# ESP_flagServer.net
KiCad netlist of a schematic drawn in EAGLE
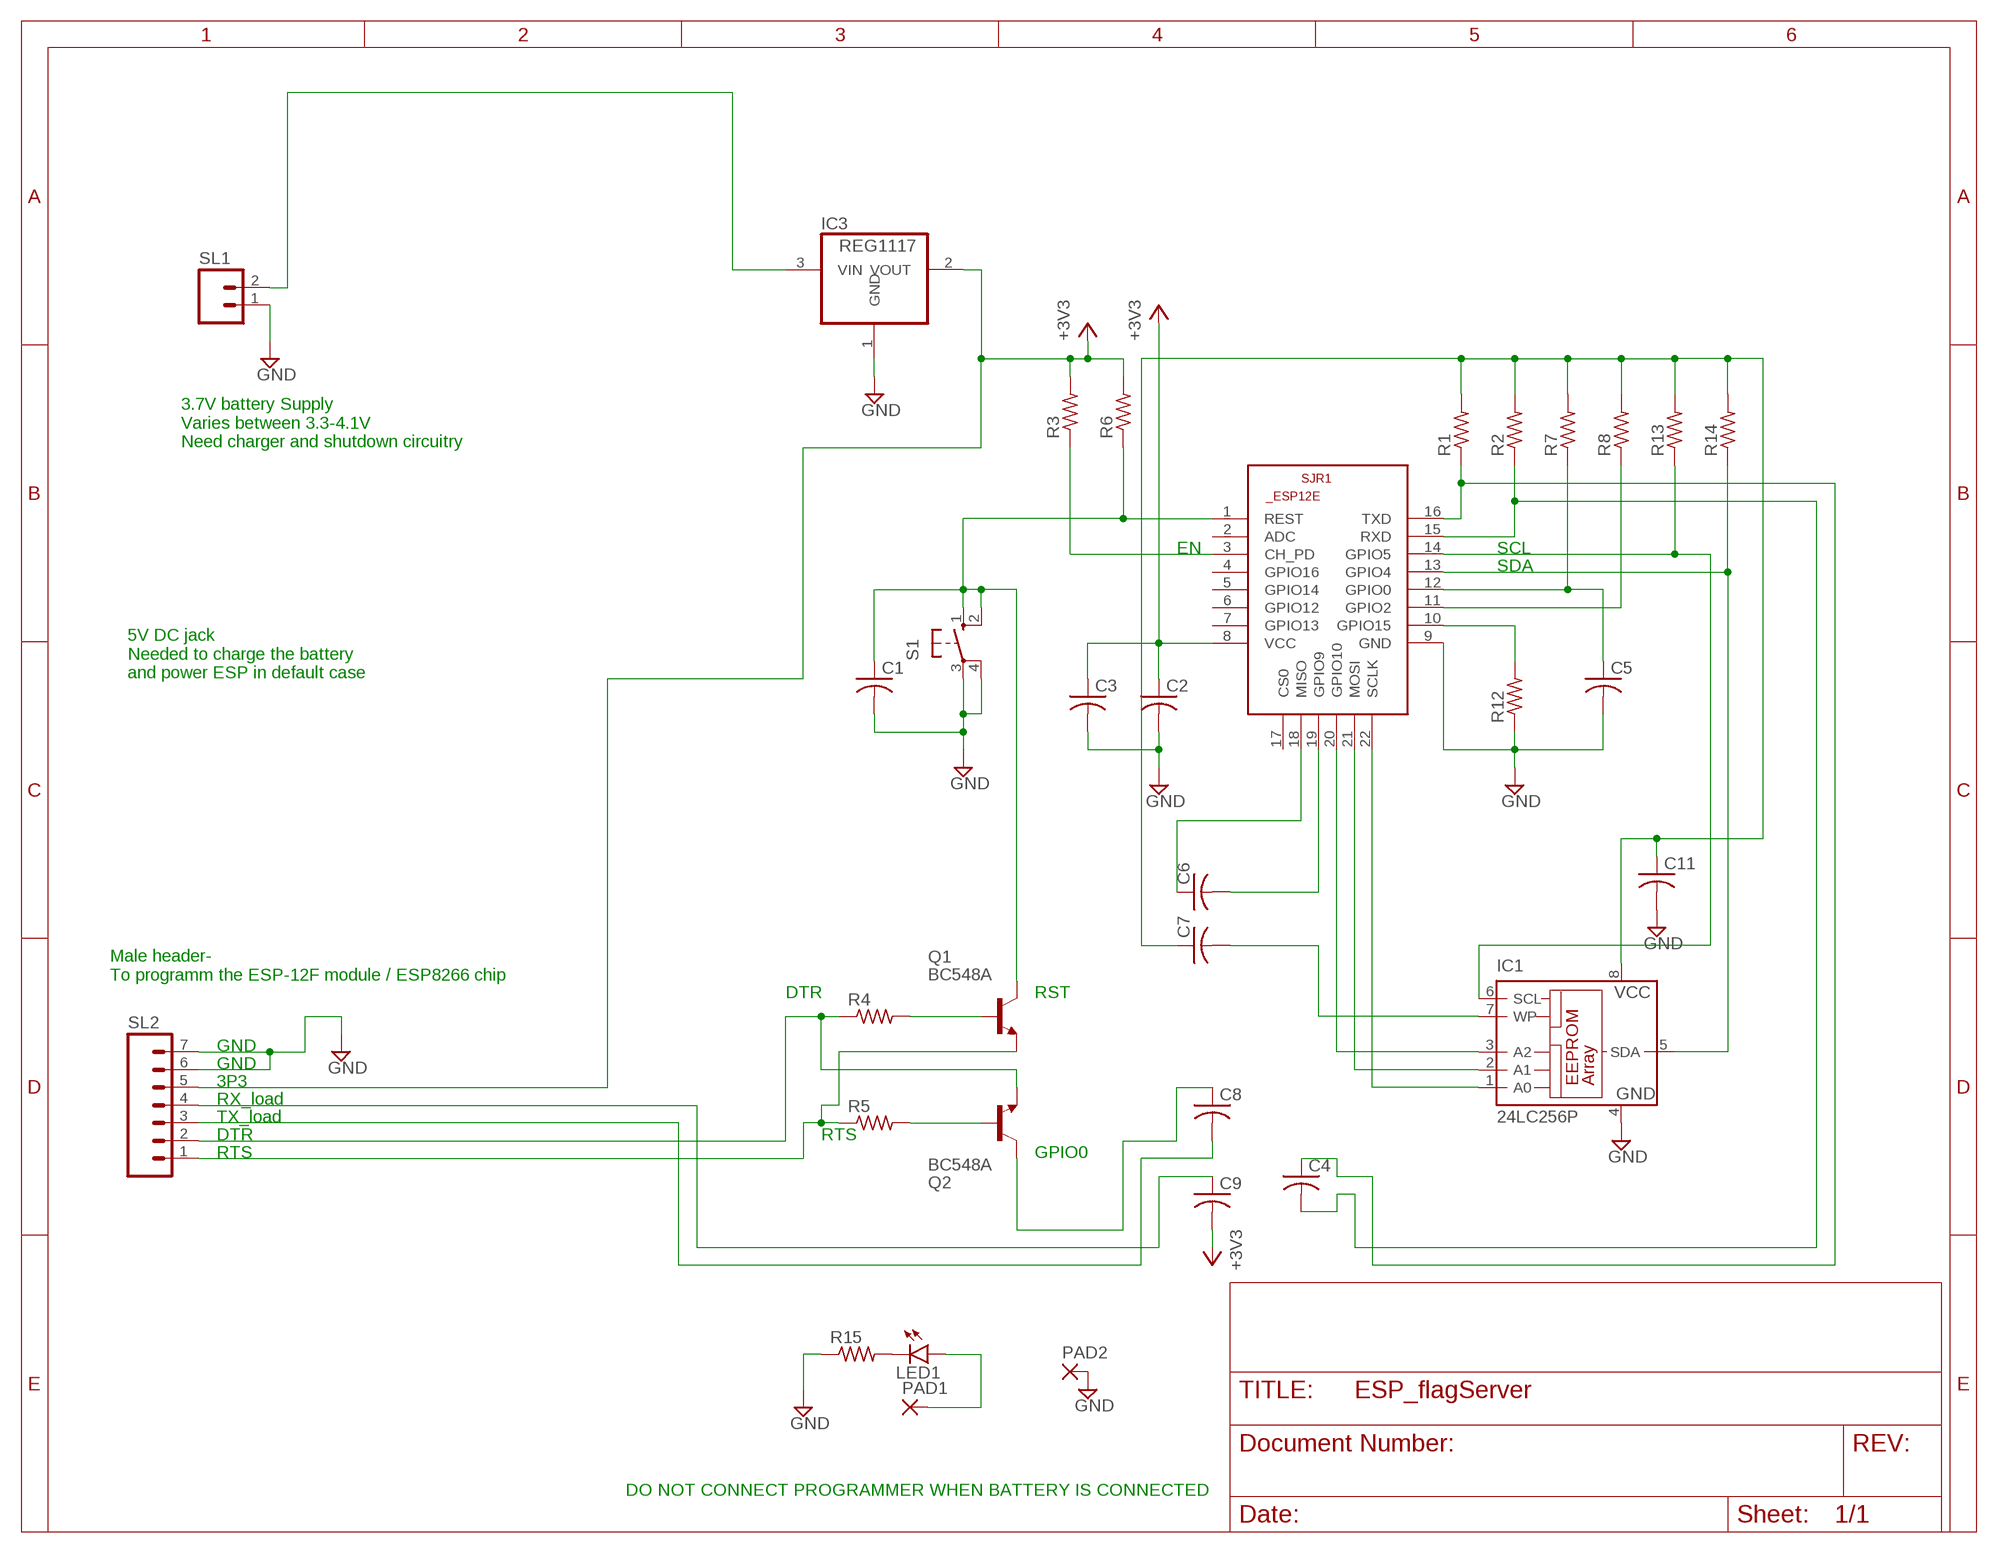
[diagram p0: schematic, sheet 1]

(export (version "E")
  (design (tool "Eeschema 10.0.6"))
  (components
    (comp (ref "C1")
      (value "C-US050-024X044")
      (footprint "eagle-import:C050-024X044")
      (libsource (lib "eagle-import") (part "C-US050-024X044"))
    )
    (comp (ref "C2")
      (value "C-US050-024X044")
      (footprint "eagle-import:C050-024X044")
      (libsource (lib "eagle-import") (part "C-US050-024X044"))
    )
    (comp (ref "C3")
      (value "C-US050-024X044")
      (footprint "eagle-import:C050-024X044")
      (libsource (lib "eagle-import") (part "C-US050-024X044"))
    )
    (comp (ref "C4")
      (value "C-US025-024X044")
      (footprint "eagle-import:C025-024X044")
      (libsource (lib "eagle-import") (part "C-US025-024X044"))
    )
    (comp (ref "C5")
      (value "C-US025-024X044")
      (footprint "eagle-import:C025-024X044")
      (libsource (lib "eagle-import") (part "C-US025-024X044"))
    )
    (comp (ref "C6")
      (value "C-US025-024X044")
      (footprint "eagle-import:C025-024X044")
      (libsource (lib "eagle-import") (part "C-US025-024X044"))
    )
    (comp (ref "C7")
      (value "C-US025-024X044")
      (footprint "eagle-import:C025-024X044")
      (libsource (lib "eagle-import") (part "C-US025-024X044"))
    )
    (comp (ref "C8")
      (value "C-US025-024X044")
      (footprint "eagle-import:C025-024X044")
      (libsource (lib "eagle-import") (part "C-US025-024X044"))
    )
    (comp (ref "C9")
      (value "C-US025-024X044")
      (footprint "eagle-import:C025-024X044")
      (libsource (lib "eagle-import") (part "C-US025-024X044"))
    )
    (comp (ref "C11")
      (value "C-US025-024X044")
      (footprint "eagle-import:C025-024X044")
      (libsource (lib "eagle-import") (part "C-US025-024X044"))
    )
    (comp (ref "IC1")
      (value "24LC256P")
      (footprint "eagle-import:DIL8")
      (fields (field (name "MF") "MICROCHIP") (field (name "MPN") "24LC256-E/P"))
      (libsource (lib "eagle-import") (part "24PLC256"))
    )
    (comp (ref "IC3")
      (value "REG1117")
      (footprint "eagle-import:SOT223")
      (libsource (lib "eagle-import") (part "REG1117"))
    )
    (comp (ref "LED1")
      (value "LED3MM")
      (footprint "eagle-import:LED3MM")
      (libsource (lib "eagle-import") (part "LED3MM"))
    )
    (comp (ref "PAD1")
      (value "2,15/1,0")
      (footprint "eagle-import:2,15_1,0")
      (libsource (lib "eagle-import") (part "2,15/1,0"))
    )
    (comp (ref "PAD2")
      (value "2,15/1,0")
      (footprint "eagle-import:2,15_1,0")
      (libsource (lib "eagle-import") (part "2,15/1,0"))
    )
    (comp (ref "Q1")
      (value "BC548A")
      (footprint "eagle-import:TO92-EBC")
      (libsource (lib "eagle-import") (part "BC548A"))
    )
    (comp (ref "Q2")
      (value "BC548A")
      (footprint "eagle-import:TO92-EBC")
      (libsource (lib "eagle-import") (part "BC548A"))
    )
    (comp (ref "R1")
      (value "R-US_0204/7")
      (footprint "eagle-import:0204_7")
      (libsource (lib "eagle-import") (part "R-US_0204/7"))
    )
    (comp (ref "R2")
      (value "R-US_0204/7")
      (footprint "eagle-import:0204_7")
      (libsource (lib "eagle-import") (part "R-US_0204/7"))
    )
    (comp (ref "R3")
      (value "R-US_0204/7")
      (footprint "eagle-import:0204_7")
      (libsource (lib "eagle-import") (part "R-US_0204/7"))
    )
    (comp (ref "R4")
      (value "R-US_0204/7")
      (footprint "eagle-import:0204_7")
      (libsource (lib "eagle-import") (part "R-US_0204/7"))
    )
    (comp (ref "R5")
      (value "R-US_0204/7")
      (footprint "eagle-import:0204_7")
      (libsource (lib "eagle-import") (part "R-US_0204/7"))
    )
    (comp (ref "R6")
      (value "R-US_0204/7")
      (footprint "eagle-import:0204_7")
      (libsource (lib "eagle-import") (part "R-US_0204/7"))
    )
    (comp (ref "R7")
      (value "R-US_0204/7")
      (footprint "eagle-import:0204_7")
      (libsource (lib "eagle-import") (part "R-US_0204/7"))
    )
    (comp (ref "R8")
      (value "R-US_0204/7")
      (footprint "eagle-import:0204_7")
      (libsource (lib "eagle-import") (part "R-US_0204/7"))
    )
    (comp (ref "R12")
      (value "R-US_0204/7")
      (footprint "eagle-import:0204_7")
      (libsource (lib "eagle-import") (part "R-US_0204/7"))
    )
    (comp (ref "R13")
      (value "R-US_0204/7")
      (footprint "eagle-import:0204_7")
      (libsource (lib "eagle-import") (part "R-US_0204/7"))
    )
    (comp (ref "R14")
      (value "R-US_0204/7")
      (footprint "eagle-import:0204_7")
      (libsource (lib "eagle-import") (part "R-US_0204/7"))
    )
    (comp (ref "R15")
      (value "R-US_0204/7")
      (footprint "eagle-import:0204_7")
      (libsource (lib "eagle-import") (part "R-US_0204/7"))
    )
    (comp (ref "S1")
      (value "10-XX")
      (footprint "eagle-import:B3F-10XX")
      (fields (field (name "MPN") "B3F-1000"))
      (libsource (lib "eagle-import") (part "10-XX"))
    )
    (comp (ref "SJR1")
      (value "ESP8266-12EESP12E")
      (footprint "eagle-import:ESP8266-ESP12E")
      (libsource (lib "eagle-import") (part "ESP8266-12EESP12E"))
    )
    (comp (ref "SL1")
      (value "M02")
      (footprint "eagle-import:02P")
      (libsource (lib "eagle-import") (part "M02"))
    )
    (comp (ref "SL2")
      (value "M07")
      (footprint "eagle-import:07P")
      (libsource (lib "eagle-import") (part "M07"))
    )
  )
  (nets
    (net (code "1") (name "+3V3") (class "Default")
      (node (ref "C2") (pin "1") (pinfunction "1_1") (pintype "passive"))
      (node (ref "C3") (pin "1") (pinfunction "1_1") (pintype "passive"))
      (node (ref "C9") (pin "2") (pinfunction "2_2") (pintype "passive"))
      (node (ref "IC3") (pin "2") (pinfunction "VOUT_2") (pintype "output"))
      (node (ref "R3") (pin "2") (pinfunction "2_2") (pintype "passive"))
      (node (ref "R6") (pin "2") (pinfunction "2_2") (pintype "passive"))
      (node (ref "SJR1") (pin "8") (pinfunction "VCC_8") (pintype "bidirectional"))
      (node (ref "SL2") (pin "5") (pinfunction "5_5") (pintype "passive"))
    )
    (net (code "2") (name "GND") (class "Default")
      (node (ref "C1") (pin "2") (pinfunction "2_2") (pintype "passive"))
      (node (ref "C11") (pin "2") (pinfunction "2_2") (pintype "passive"))
      (node (ref "C2") (pin "2") (pinfunction "2_2") (pintype "passive"))
      (node (ref "C3") (pin "2") (pinfunction "2_2") (pintype "passive"))
      (node (ref "C5") (pin "2") (pinfunction "2_2") (pintype "passive"))
      (node (ref "IC1") (pin "4") (pinfunction "GND_4") (pintype "power_in"))
      (node (ref "IC3") (pin "1") (pinfunction "GND_1") (pintype "power_in"))
      (node (ref "PAD2") (pin "1") (pinfunction "P_1") (pintype "passive"))
      (node (ref "R12") (pin "1") (pinfunction "1_1") (pintype "passive"))
      (node (ref "R15") (pin "1") (pinfunction "1_1") (pintype "passive"))
      (node (ref "S1") (pin "3") (pinfunction "P_3") (pintype "passive"))
      (node (ref "S1") (pin "4") (pinfunction "P1_4") (pintype "passive"))
      (node (ref "SJR1") (pin "9") (pinfunction "GND_9") (pintype "bidirectional"))
      (node (ref "SL1") (pin "1") (pinfunction "1_1") (pintype "passive"))
      (node (ref "SL2") (pin "6") (pinfunction "6_6") (pintype "passive"))
      (node (ref "SL2") (pin "7") (pinfunction "7_7") (pintype "passive"))
    )
    (net (code "3") (name "Net-(C8-Pad1)") (class "Default")
      (node (ref "C8") (pin "1") (pinfunction "1_1") (pintype "passive"))
      (node (ref "Q2") (pin "C") (pinfunction "C_C") (pintype "passive"))
    )
    (net (code "4") (name "Net-(C8-Pad2)") (class "Default")
      (node (ref "C8") (pin "2") (pinfunction "2_2") (pintype "passive"))
      (node (ref "SL2") (pin "3") (pinfunction "3_3") (pintype "passive"))
    )
    (net (code "5") (name "Net-(C9-Pad1)") (class "Default")
      (node (ref "C9") (pin "1") (pinfunction "1_1") (pintype "passive"))
      (node (ref "SL2") (pin "4") (pinfunction "4_4") (pintype "passive"))
    )
    (net (code "6") (name "Net-(IC1-A0)") (class "Default")
      (node (ref "IC1") (pin "1") (pinfunction "A0_1") (pintype "input"))
      (node (ref "SJR1") (pin "22") (pinfunction "SCLK_22") (pintype "bidirectional"))
    )
    (net (code "7") (name "Net-(IC1-A1)") (class "Default")
      (node (ref "IC1") (pin "2") (pinfunction "A1_2") (pintype "input"))
      (node (ref "SJR1") (pin "21") (pinfunction "MOSI_21") (pintype "bidirectional"))
    )
    (net (code "8") (name "Net-(IC1-A2)") (class "Default")
      (node (ref "IC1") (pin "3") (pinfunction "A2_3") (pintype "input"))
      (node (ref "SJR1") (pin "20") (pinfunction "GPIO10_20") (pintype "bidirectional"))
    )
    (net (code "9") (name "Net-(IC1-SCL)") (class "Default")
      (node (ref "IC1") (pin "6") (pinfunction "SCL_6") (pintype "input"))
      (node (ref "R13") (pin "1") (pinfunction "1_1") (pintype "passive"))
      (node (ref "SJR1") (pin "14") (pinfunction "GPIO5_14") (pintype "bidirectional"))
    )
    (net (code "10") (name "Net-(IC1-SDA)") (class "Default")
      (node (ref "IC1") (pin "5") (pinfunction "SDA_5") (pintype "bidirectional"))
      (node (ref "R14") (pin "1") (pinfunction "1_1") (pintype "passive"))
      (node (ref "SJR1") (pin "13") (pinfunction "GPIO4_13") (pintype "bidirectional"))
    )
    (net (code "11") (name "Net-(IC1-VCC)") (class "Default")
      (node (ref "C11") (pin "1") (pinfunction "1_1") (pintype "passive"))
      (node (ref "C7") (pin "1") (pinfunction "1_1") (pintype "passive"))
      (node (ref "IC1") (pin "8") (pinfunction "VCC_8") (pintype "power_in"))
      (node (ref "R1") (pin "2") (pinfunction "2_2") (pintype "passive"))
      (node (ref "R13") (pin "2") (pinfunction "2_2") (pintype "passive"))
      (node (ref "R14") (pin "2") (pinfunction "2_2") (pintype "passive"))
      (node (ref "R2") (pin "2") (pinfunction "2_2") (pintype "passive"))
      (node (ref "R7") (pin "2") (pinfunction "2_2") (pintype "passive"))
      (node (ref "R8") (pin "2") (pinfunction "2_2") (pintype "passive"))
    )
    (net (code "12") (name "Net-(IC1-WP)") (class "Default")
      (node (ref "C7") (pin "2") (pinfunction "2_2") (pintype "passive"))
      (node (ref "IC1") (pin "7") (pinfunction "WP_7") (pintype "input"))
    )
    (net (code "13") (name "Net-(IC3-VIN)") (class "Default")
      (node (ref "IC3") (pin "3") (pinfunction "VIN_3") (pintype "input"))
      (node (ref "SL1") (pin "2") (pinfunction "2_2") (pintype "passive"))
    )
    (net (code "14") (name "Net-(LED1-C)") (class "Default")
      (node (ref "LED1") (pin "K") (pinfunction "C_K") (pintype "passive"))
      (node (ref "R15") (pin "2") (pinfunction "2_2") (pintype "passive"))
    )
    (net (code "15") (name "Net-(PAD1-P)") (class "Default")
      (node (ref "LED1") (pin "A") (pinfunction "A_A") (pintype "passive"))
      (node (ref "PAD1") (pin "1") (pinfunction "P_1") (pintype "passive"))
    )
    (net (code "16") (name "Net-(Q1-PadB)") (class "Default")
      (node (ref "Q1") (pin "B") (pinfunction "B_B") (pintype "passive"))
      (node (ref "R4") (pin "2") (pinfunction "2_2") (pintype "passive"))
    )
    (net (code "17") (name "Net-(Q1-PadE)") (class "Default")
      (node (ref "Q1") (pin "E") (pinfunction "E_E") (pintype "passive"))
      (node (ref "R5") (pin "1") (pinfunction "1_1") (pintype "passive"))
      (node (ref "SL2") (pin "1") (pinfunction "1_1") (pintype "passive"))
    )
    (net (code "18") (name "Net-(Q2-PadB)") (class "Default")
      (node (ref "Q2") (pin "B") (pinfunction "B_B") (pintype "passive"))
      (node (ref "R5") (pin "2") (pinfunction "2_2") (pintype "passive"))
    )
    (net (code "19") (name "Net-(Q2-PadE)") (class "Default")
      (node (ref "Q2") (pin "E") (pinfunction "E_E") (pintype "passive"))
      (node (ref "R4") (pin "1") (pinfunction "1_1") (pintype "passive"))
      (node (ref "SL2") (pin "2") (pinfunction "2_2") (pintype "passive"))
    )
    (net (code "20") (name "Net-(S1-S)") (class "Default")
      (node (ref "C1") (pin "1") (pinfunction "1_1") (pintype "passive"))
      (node (ref "Q1") (pin "C") (pinfunction "C_C") (pintype "passive"))
      (node (ref "R6") (pin "1") (pinfunction "1_1") (pintype "passive"))
      (node (ref "S1") (pin "1") (pinfunction "S_1") (pintype "passive"))
      (node (ref "S1") (pin "2") (pinfunction "S1_2") (pintype "passive"))
      (node (ref "SJR1") (pin "1") (pinfunction "REST_1") (pintype "bidirectional"))
    )
    (net (code "21") (name "Net-(SJR1-CH_PD)") (class "Default")
      (node (ref "R3") (pin "1") (pinfunction "1_1") (pintype "passive"))
      (node (ref "SJR1") (pin "3") (pinfunction "CH_PD_3") (pintype "bidirectional"))
    )
    (net (code "22") (name "Net-(SJR1-GPIO0)") (class "Default")
      (node (ref "C5") (pin "1") (pinfunction "1_1") (pintype "passive"))
      (node (ref "R7") (pin "1") (pinfunction "1_1") (pintype "passive"))
      (node (ref "SJR1") (pin "12") (pinfunction "GPIO0_12") (pintype "bidirectional"))
    )
    (net (code "23") (name "Net-(SJR1-GPIO2)") (class "Default")
      (node (ref "R8") (pin "1") (pinfunction "1_1") (pintype "passive"))
      (node (ref "SJR1") (pin "11") (pinfunction "GPIO2_11") (pintype "bidirectional"))
    )
    (net (code "24") (name "Net-(SJR1-GPIO9)") (class "Default")
      (node (ref "C6") (pin "2") (pinfunction "2_2") (pintype "passive"))
      (node (ref "SJR1") (pin "19") (pinfunction "GPIO9_19") (pintype "bidirectional"))
    )
    (net (code "25") (name "Net-(SJR1-GPIO15)") (class "Default")
      (node (ref "R12") (pin "2") (pinfunction "2_2") (pintype "passive"))
      (node (ref "SJR1") (pin "10") (pinfunction "GPIO15_10") (pintype "bidirectional"))
    )
    (net (code "26") (name "Net-(SJR1-MISO)") (class "Default")
      (node (ref "C6") (pin "1") (pinfunction "1_1") (pintype "passive"))
      (node (ref "SJR1") (pin "18") (pinfunction "MISO_18") (pintype "bidirectional"))
    )
    (net (code "27") (name "Net-(SJR1-RXD)") (class "Default")
      (node (ref "C4") (pin "2") (pinfunction "2_2") (pintype "passive"))
      (node (ref "R2") (pin "1") (pinfunction "1_1") (pintype "passive"))
      (node (ref "SJR1") (pin "15") (pinfunction "RXD_15") (pintype "bidirectional"))
    )
    (net (code "28") (name "Net-(SJR1-TXD)") (class "Default")
      (node (ref "C4") (pin "1") (pinfunction "1_1") (pintype "passive"))
      (node (ref "R1") (pin "1") (pinfunction "1_1") (pintype "passive"))
      (node (ref "SJR1") (pin "16") (pinfunction "TXD_16") (pintype "bidirectional"))
    )
    (net (code "29") (name "unconnected-(SJR1-ADC-Pad2)") (class "Default")
      (node (ref "SJR1") (pin "2") (pinfunction "ADC_2") (pintype "bidirectional"))
    )
    (net (code "30") (name "unconnected-(SJR1-CS0-Pad17)") (class "Default")
      (node (ref "SJR1") (pin "17") (pinfunction "CS0_17") (pintype "bidirectional"))
    )
    (net (code "31") (name "unconnected-(SJR1-GPIO12-Pad6)") (class "Default")
      (node (ref "SJR1") (pin "6") (pinfunction "GPIO12_6") (pintype "bidirectional"))
    )
    (net (code "32") (name "unconnected-(SJR1-GPIO13-Pad7)") (class "Default")
      (node (ref "SJR1") (pin "7") (pinfunction "GPIO13_7") (pintype "bidirectional"))
    )
    (net (code "33") (name "unconnected-(SJR1-GPIO14-Pad5)") (class "Default")
      (node (ref "SJR1") (pin "5") (pinfunction "GPIO14_5") (pintype "bidirectional"))
    )
    (net (code "34") (name "unconnected-(SJR1-GPIO16-Pad4)") (class "Default")
      (node (ref "SJR1") (pin "4") (pinfunction "GPIO16_4") (pintype "bidirectional"))
    )
  )
)
